# Output.net
KiCad netlist of a schematic drawn in Altium Designer
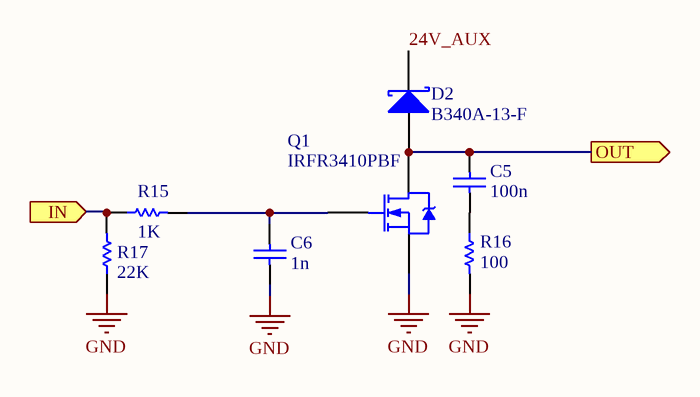
[diagram p0: Output.SchDoc]

(export (version "E")
  (design (tool "Eeschema 10.0.6"))
  (components
    (comp (ref "C5")
      (value "100n")
      (footprint "SMT0805_M")
      (description "Capacitor")
      (fields (field (name "Comment") "X7R/0805/50V") (field (name "PUBLISHER") "Altium Limited"))
      (libsource (lib "Miscellaneous Devices") (part "Cap"))
    )
    (comp (ref "C6")
      (value "1n")
      (footprint "SMT0805_M")
      (description "Capacitor")
      (fields (field (name "Comment") "X7R/0805/50V") (field (name "PUBLISHER") "Altium Limited"))
      (libsource (lib "Miscellaneous Devices") (part "Cap"))
    )
    (comp (ref "D2")
      (value "B340A-13-F")
      (footprint "SMB")
      (description "Schottky Diode")
      (libsource (lib "Miscellaneous Devices") (part "D Schottky"))
    )
    (comp (ref "Q1")
      (value "IRFR3410PBF")
      (footprint "TO-252AA_M")
      (description "HEXFET Power MOSFET")
      (libsource (lib "IR Discrete MOSFET - Power") (part "IRFR1N60A"))
    )
    (comp (ref "R15")
      (value "1K")
      (footprint "SMT0805_M")
      (description "Resistor")
      (fields (field (name "Comment") "0805/.125W/5Q") (field (name "PUBLISHER") "Altium Limited"))
      (libsource (lib "Miscellaneous Devices") (part "Res1"))
    )
    (comp (ref "R16")
      (value "100")
      (footprint "SMT0805_M")
      (description "Resistor")
      (fields (field (name "Comment") "0805/.125W/5Q") (field (name "PUBLISHER") "Altium Limited"))
      (libsource (lib "Miscellaneous Devices") (part "Res1"))
    )
    (comp (ref "R17")
      (value "22K")
      (footprint "SMT0805_M")
      (description "Resistor")
      (fields (field (name "Comment") "0805/.125W/5Q") (field (name "PUBLISHER") "Altium Limited"))
      (libsource (lib "Miscellaneous Devices") (part "Res1"))
    )
  )
  (nets
    (net (code "1") (name "/24V_AUX") (class "Default")
      (node (ref "D2") (pin "2") (pinfunction "K_2") (pintype "passive"))
    )
    (net (code "2") (name "/IN") (class "Default")
      (node (ref "R15") (pin "1") (pinfunction "1_1") (pintype "passive"))
      (node (ref "R17") (pin "2") (pinfunction "2_2") (pintype "passive"))
    )
    (net (code "3") (name "/OUT") (class "Default")
      (node (ref "C5") (pin "2") (pinfunction "2_2") (pintype "passive"))
      (node (ref "D2") (pin "1") (pinfunction "A_1") (pintype "passive"))
      (node (ref "Q1") (pin "4") (pinfunction "D_4") (pintype "passive"))
    )
    (net (code "4") (name "GND") (class "Default")
      (node (ref "C6") (pin "1") (pinfunction "1_1") (pintype "passive"))
      (node (ref "Q1") (pin "3") (pinfunction "S_3") (pintype "passive"))
      (node (ref "R16") (pin "2") (pinfunction "2_2") (pintype "passive"))
      (node (ref "R17") (pin "1") (pinfunction "1_1") (pintype "passive"))
    )
    (net (code "5") (name "Net-(C5-Pad1)") (class "Default")
      (node (ref "C5") (pin "1") (pinfunction "1_1") (pintype "passive"))
      (node (ref "R16") (pin "1") (pinfunction "1_1") (pintype "passive"))
    )
    (net (code "6") (name "Net-(Q1-G)") (class "Default")
      (node (ref "C6") (pin "2") (pinfunction "2_2") (pintype "passive"))
      (node (ref "Q1") (pin "1") (pinfunction "G_1") (pintype "passive"))
      (node (ref "R15") (pin "2") (pinfunction "2_2") (pintype "passive"))
    )
  )
)
